# TD-01_Mk3.net
KiCad netlist of a schematic drawn in EasyEDA
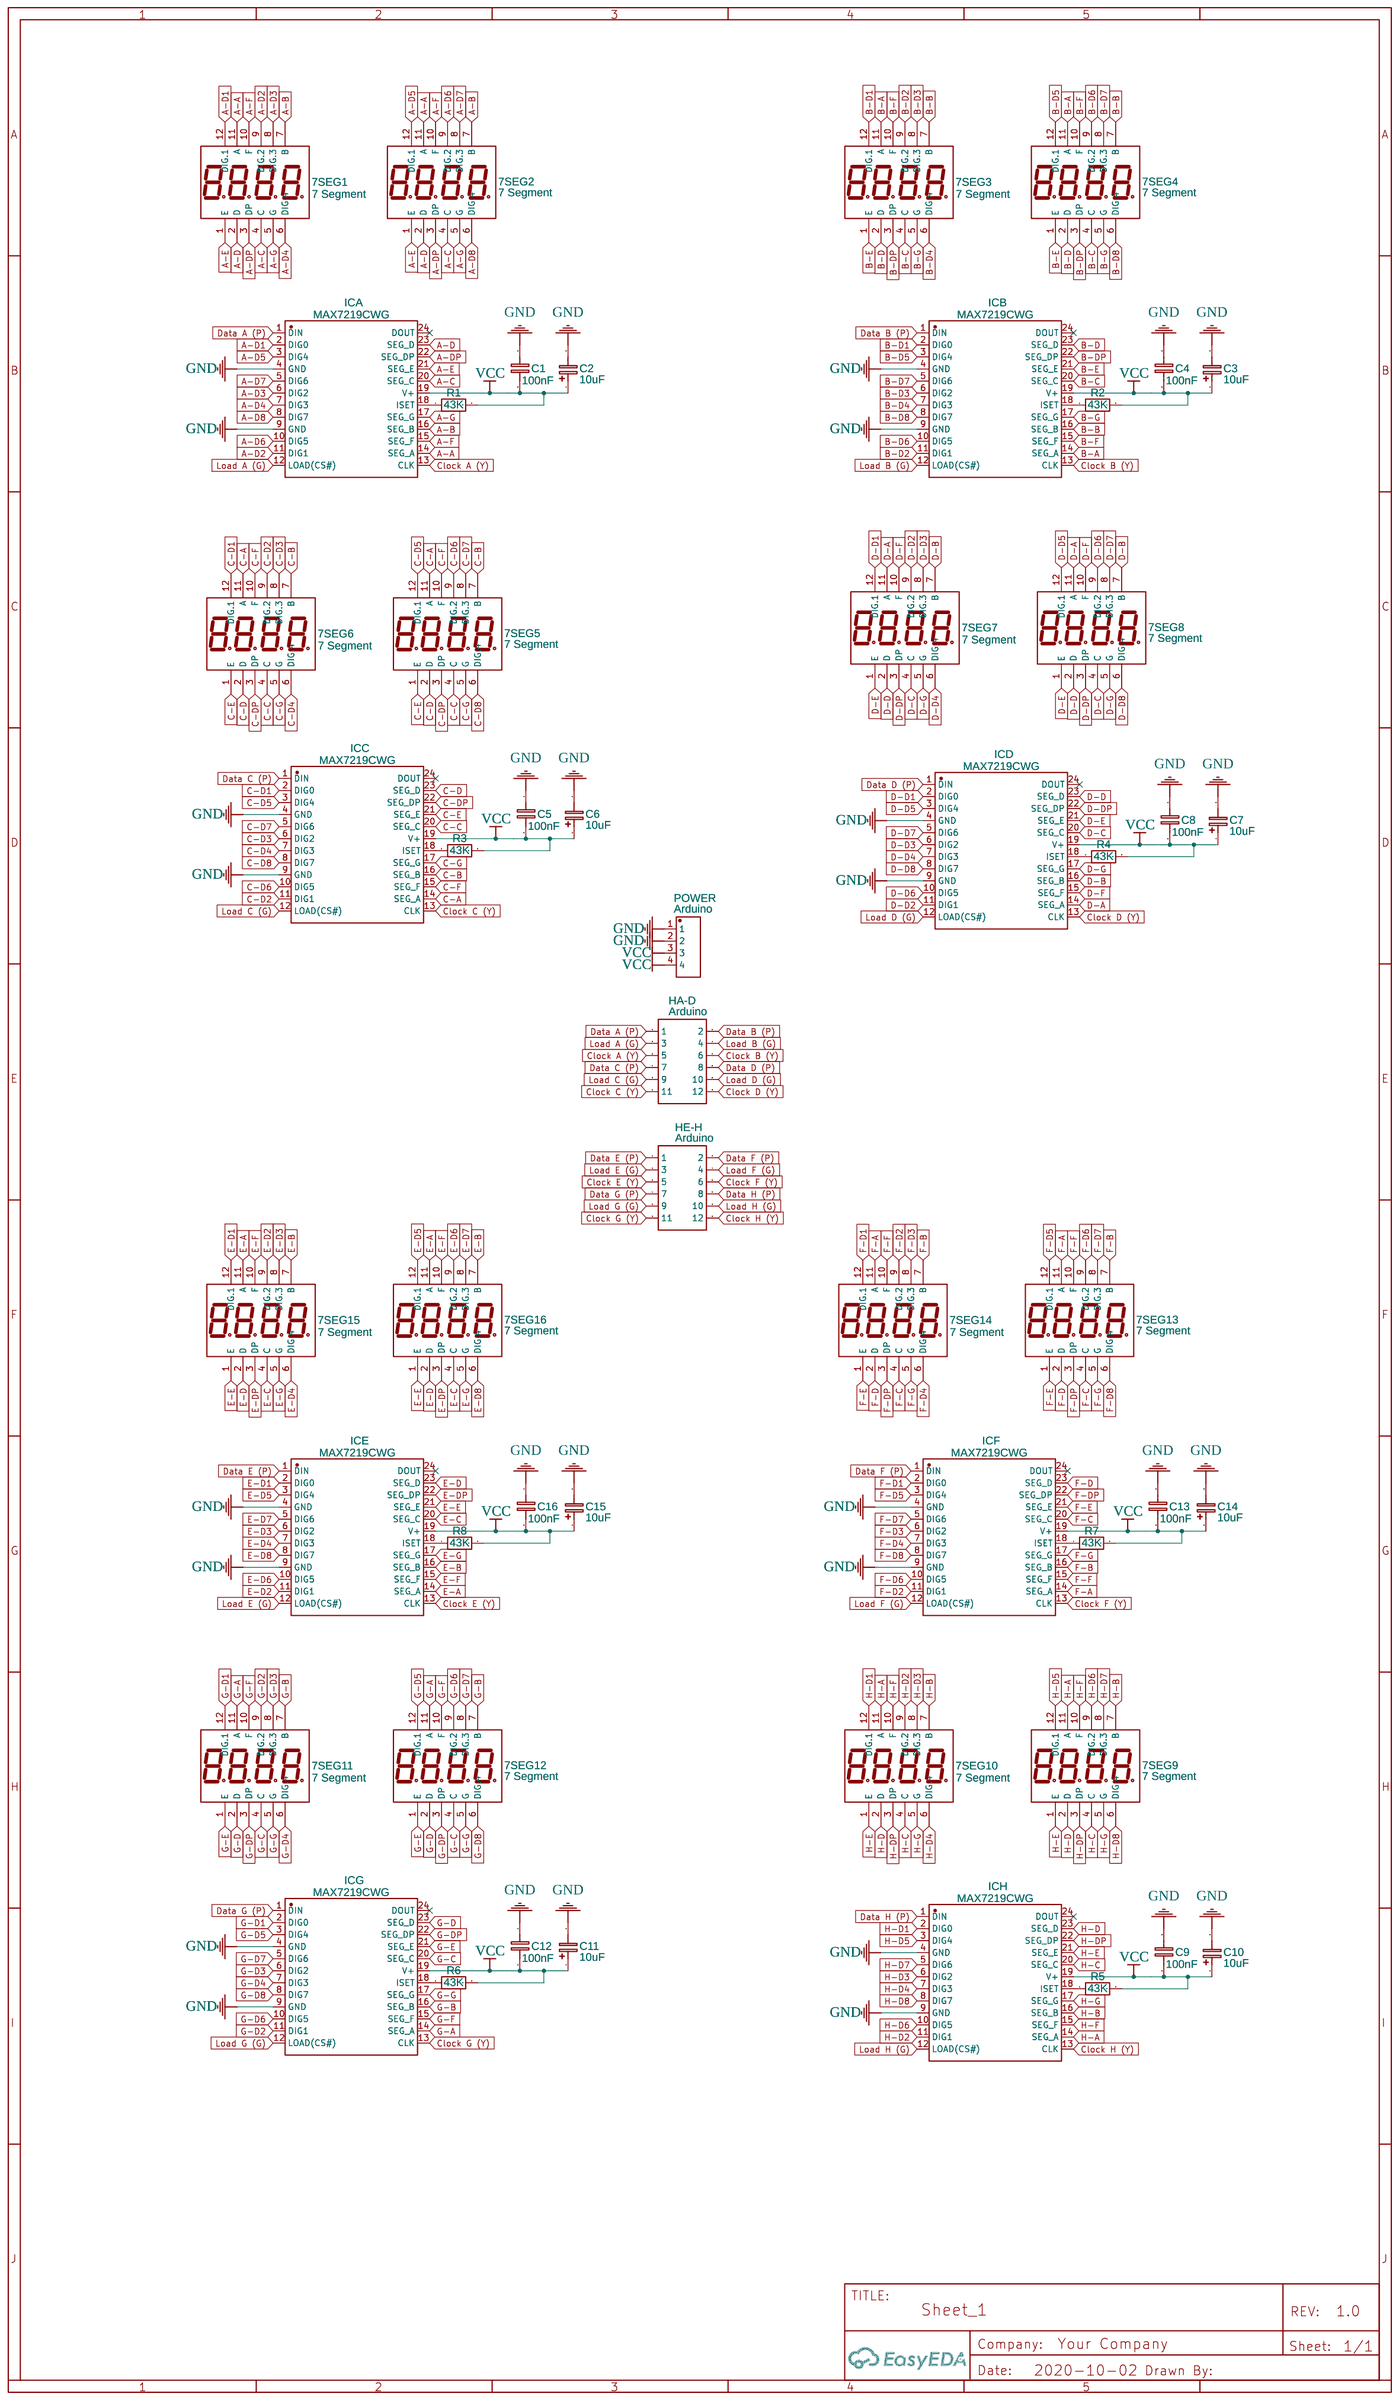
[diagram p0: schematic sheet]

(export (version "E")
  (design (tool "Eeschema 10.0.6"))
  (components
    (comp (ref "7SEG1")
      (value "7 Segment")
      (fields
        (field (name "BOM_Manufacturer Part") "TOF-5461AMR-B17.5")
        (field (name "BOM_Supplier Part") "C417345")
      )
      (libsource (lib "") (part "TOF-5461AMR-B17.5"))
    )
    (comp (ref "7SEG2")
      (value "7 Segment")
      (fields
        (field (name "BOM_Manufacturer Part") "TOF-5461AMR-B17.5")
        (field (name "BOM_Supplier Part") "C417345")
      )
      (libsource (lib "") (part "TOF-5461AMR-B17.5"))
    )
    (comp (ref "7SEG3")
      (value "7 Segment")
      (fields
        (field (name "BOM_Manufacturer Part") "TOF-5461AMR-B17.5")
        (field (name "BOM_Supplier Part") "C417345")
      )
      (libsource (lib "") (part "TOF-5461AMR-B17.5"))
    )
    (comp (ref "7SEG4")
      (value "7 Segment")
      (fields
        (field (name "BOM_Manufacturer Part") "TOF-5461AMR-B17.5")
        (field (name "BOM_Supplier Part") "C417345")
      )
      (libsource (lib "") (part "TOF-5461AMR-B17.5"))
    )
    (comp (ref "7SEG5")
      (value "7 Segment")
      (fields
        (field (name "BOM_Manufacturer Part") "TOF-5461AMR-B17.5")
        (field (name "BOM_Supplier Part") "C417345")
      )
      (libsource (lib "") (part "TOF-5461AMR-B17.5"))
    )
    (comp (ref "7SEG6")
      (value "7 Segment")
      (fields
        (field (name "BOM_Manufacturer Part") "TOF-5461AMR-B17.5")
        (field (name "BOM_Supplier Part") "C417345")
      )
      (libsource (lib "") (part "TOF-5461AMR-B17.5"))
    )
    (comp (ref "7SEG7")
      (value "7 Segment")
      (fields
        (field (name "BOM_Manufacturer Part") "TOF-5461AMR-B17.5")
        (field (name "BOM_Supplier Part") "C417345")
      )
      (libsource (lib "") (part "TOF-5461AMR-B17.5"))
    )
    (comp (ref "7SEG8")
      (value "7 Segment")
      (fields
        (field (name "BOM_Manufacturer Part") "TOF-5461AMR-B17.5")
        (field (name "BOM_Supplier Part") "C417345")
      )
      (libsource (lib "") (part "TOF-5461AMR-B17.5"))
    )
    (comp (ref "7SEG9")
      (value "7 Segment")
      (fields
        (field (name "BOM_Manufacturer Part") "TOF-5461AMR-B17.5")
        (field (name "BOM_Supplier Part") "C417345")
      )
      (libsource (lib "") (part "TOF-5461AMR-B17.5"))
    )
    (comp (ref "7SEG10")
      (value "7 Segment")
      (fields
        (field (name "BOM_Manufacturer Part") "TOF-5461AMR-B17.5")
        (field (name "BOM_Supplier Part") "C417345")
      )
      (libsource (lib "") (part "TOF-5461AMR-B17.5"))
    )
    (comp (ref "7SEG11")
      (value "7 Segment")
      (fields
        (field (name "BOM_Manufacturer Part") "TOF-5461AMR-B17.5")
        (field (name "BOM_Supplier Part") "C417345")
      )
      (libsource (lib "") (part "TOF-5461AMR-B17.5"))
    )
    (comp (ref "7SEG12")
      (value "7 Segment")
      (fields
        (field (name "BOM_Manufacturer Part") "TOF-5461AMR-B17.5")
        (field (name "BOM_Supplier Part") "C417345")
      )
      (libsource (lib "") (part "TOF-5461AMR-B17.5"))
    )
    (comp (ref "7SEG13")
      (value "7 Segment")
      (fields
        (field (name "BOM_Manufacturer Part") "TOF-5461AMR-B17.5")
        (field (name "BOM_Supplier Part") "C417345")
      )
      (libsource (lib "") (part "TOF-5461AMR-B17.5"))
    )
    (comp (ref "7SEG14")
      (value "7 Segment")
      (fields
        (field (name "BOM_Manufacturer Part") "TOF-5461AMR-B17.5")
        (field (name "BOM_Supplier Part") "C417345")
      )
      (libsource (lib "") (part "TOF-5461AMR-B17.5"))
    )
    (comp (ref "7SEG15")
      (value "7 Segment")
      (fields
        (field (name "BOM_Manufacturer Part") "TOF-5461AMR-B17.5")
        (field (name "BOM_Supplier Part") "C417345")
      )
      (libsource (lib "") (part "TOF-5461AMR-B17.5"))
    )
    (comp (ref "7SEG16")
      (value "7 Segment")
      (fields
        (field (name "BOM_Manufacturer Part") "TOF-5461AMR-B17.5")
        (field (name "BOM_Supplier Part") "C417345")
      )
      (libsource (lib "") (part "TOF-5461AMR-B17.5"))
    )
    (comp (ref "C1") (value "100nF") (libsource (lib "") (part "C_0603_EU_1")))
    (comp (ref "C2") (value "10uF") (libsource (lib "") (part "C_Tan_SMD_A_EU_5")))
    (comp (ref "C3") (value "10uF") (libsource (lib "") (part "C_Tan_SMD_A_EU_1")))
    (comp (ref "C4") (value "100nF") (libsource (lib "") (part "C_0603_EU_2")))
    (comp (ref "C5") (value "100nF") (libsource (lib "") (part "C_0603_EU_3")))
    (comp (ref "C6") (value "10uF") (libsource (lib "") (part "C_Tan_SMD_A_EU_4")))
    (comp (ref "C7") (value "10uF") (libsource (lib "") (part "C_Tan_SMD_A_EU_3")))
    (comp (ref "C8") (value "100nF") (libsource (lib "") (part "C_0603_EU")))
    (comp (ref "C9") (value "100nF") (libsource (lib "") (part "C_0603_EU")))
    (comp (ref "C10") (value "10uF") (libsource (lib "") (part "C_Tan_SMD_A_EU_2")))
    (comp (ref "C11") (value "10uF") (libsource (lib "") (part "C_Tan_SMD_A_EU")))
    (comp (ref "C12") (value "100nF") (libsource (lib "") (part "C_0603_EU_3")))
    (comp (ref "C13") (value "100nF") (libsource (lib "") (part "C_0603_EU")))
    (comp (ref "C14") (value "10uF") (libsource (lib "") (part "C_Tan_SMD_A_EU_2")))
    (comp (ref "C15") (value "10uF") (libsource (lib "") (part "C_Tan_SMD_A_EU")))
    (comp (ref "C16") (value "100nF") (libsource (lib "") (part "C_0603_EU_3")))
    (comp (ref "HA-D")
      (value "Arduino")
      (fields
        (field (name "BOM_Manufacturer Part") "Header-Female-2.54_2x6")
        (field (name "BOM_Supplier Part") "C36191")
      )
      (libsource (lib "") (part "Header-Female-2.54_2x6"))
    )
    (comp (ref "HE-H")
      (value "Arduino")
      (fields
        (field (name "BOM_Manufacturer Part") "Header-Female-2.54_2x6")
        (field (name "BOM_Supplier Part") "C36191")
      )
      (libsource (lib "") (part "Header-Female-2.54_2x6_1"))
    )
    (comp (ref "ICA")
      (value "MAX7219CWG")
      (fields (field (name "BOM_Supplier Part") "C9964"))
      (libsource (lib "") (part "MAX7219CWG_3"))
    )
    (comp (ref "ICB")
      (value "MAX7219CWG")
      (fields (field (name "BOM_Supplier Part") "C9964"))
      (libsource (lib "") (part "MAX7219CWG_7"))
    )
    (comp (ref "ICC")
      (value "MAX7219CWG")
      (fields (field (name "BOM_Supplier Part") "C9964"))
      (libsource (lib "") (part "MAX7219CWG_6"))
    )
    (comp (ref "ICD")
      (value "MAX7219CWG")
      (fields (field (name "BOM_Supplier Part") "C9964"))
      (libsource (lib "") (part "MAX7219CWG_5"))
    )
    (comp (ref "ICE")
      (value "MAX7219CWG")
      (fields (field (name "BOM_Supplier Part") "C9964"))
      (libsource (lib "") (part "MAX7219CWG_4"))
    )
    (comp (ref "ICF")
      (value "MAX7219CWG")
      (fields (field (name "BOM_Supplier Part") "C9964"))
      (libsource (lib "") (part "MAX7219CWG_1"))
    )
    (comp (ref "ICG")
      (value "MAX7219CWG")
      (fields (field (name "BOM_Supplier Part") "C9964"))
      (libsource (lib "") (part "MAX7219CWG"))
    )
    (comp (ref "ICH")
      (value "MAX7219CWG")
      (fields (field (name "BOM_Supplier Part") "C9964"))
      (libsource (lib "") (part "MAX7219CWG_2"))
    )
    (comp (ref "POWER")
      (value "Arduino")
      (fields
        (field (name "BOM_Manufacturer Part") "Headers  Pins 1*4P")
        (field (name "BOM_Supplier Part") "C59481")
      )
      (libsource (lib "") (part "Header-Male-2.54_1x4_C59481"))
    )
    (comp (ref "R1") (value "43K") (libsource (lib "") (part "R_0603_EU")))
    (comp (ref "R2") (value "43K") (libsource (lib "") (part "R_0603_EU")))
    (comp (ref "R3") (value "43K") (libsource (lib "") (part "R_0603_EU")))
    (comp (ref "R4") (value "43K") (libsource (lib "") (part "R_0603_EU")))
    (comp (ref "R5") (value "43K") (libsource (lib "") (part "R_0603_EU")))
    (comp (ref "R6") (value "43K") (libsource (lib "") (part "R_0603_EU")))
    (comp (ref "R7") (value "43K") (libsource (lib "") (part "R_0603_EU")))
    (comp (ref "R8") (value "43K") (libsource (lib "") (part "R_0603_EU")))
  )
  (nets
    (net (code "1") (name "A-A") (class "Default")
      (node (ref "7SEG1") (pin "11") (pinfunction "A_11") (pintype "unspecified"))
      (node (ref "7SEG2") (pin "11") (pinfunction "A_11") (pintype "unspecified"))
      (node (ref "ICA") (pin "14") (pinfunction "SEG_A_14") (pintype "unspecified"))
    )
    (net (code "2") (name "A-B") (class "Default")
      (node (ref "7SEG1") (pin "7") (pinfunction "B_7") (pintype "unspecified"))
      (node (ref "7SEG2") (pin "7") (pinfunction "B_7") (pintype "unspecified"))
      (node (ref "ICA") (pin "16") (pinfunction "SEG_B_16") (pintype "unspecified"))
    )
    (net (code "3") (name "A-C") (class "Default")
      (node (ref "7SEG1") (pin "4") (pinfunction "C_4") (pintype "unspecified"))
      (node (ref "7SEG2") (pin "4") (pinfunction "C_4") (pintype "unspecified"))
      (node (ref "ICA") (pin "20") (pinfunction "SEG_C_20") (pintype "unspecified"))
    )
    (net (code "4") (name "A-D") (class "Default")
      (node (ref "7SEG1") (pin "2") (pinfunction "D_2") (pintype "unspecified"))
      (node (ref "7SEG2") (pin "2") (pinfunction "D_2") (pintype "unspecified"))
      (node (ref "ICA") (pin "23") (pinfunction "SEG_D_23") (pintype "unspecified"))
    )
    (net (code "5") (name "A-D1") (class "Default")
      (node (ref "7SEG1") (pin "12") (pinfunction "DIG.1_12") (pintype "unspecified"))
      (node (ref "ICA") (pin "2") (pinfunction "DIG0_2") (pintype "unspecified"))
    )
    (net (code "6") (name "A-D2") (class "Default")
      (node (ref "7SEG1") (pin "9") (pinfunction "DIG.2_9") (pintype "unspecified"))
      (node (ref "ICA") (pin "11") (pinfunction "DIG1_11") (pintype "unspecified"))
    )
    (net (code "7") (name "A-D3") (class "Default")
      (node (ref "7SEG1") (pin "8") (pinfunction "DIG.3_8") (pintype "unspecified"))
      (node (ref "ICA") (pin "6") (pinfunction "DIG2_6") (pintype "unspecified"))
    )
    (net (code "8") (name "A-D4") (class "Default")
      (node (ref "7SEG1") (pin "6") (pinfunction "DIG.4_6") (pintype "unspecified"))
      (node (ref "ICA") (pin "7") (pinfunction "DIG3_7") (pintype "unspecified"))
    )
    (net (code "9") (name "A-D5") (class "Default")
      (node (ref "7SEG2") (pin "12") (pinfunction "DIG.1_12") (pintype "unspecified"))
      (node (ref "ICA") (pin "3") (pinfunction "DIG4_3") (pintype "unspecified"))
    )
    (net (code "10") (name "A-D6") (class "Default")
      (node (ref "7SEG2") (pin "9") (pinfunction "DIG.2_9") (pintype "unspecified"))
      (node (ref "ICA") (pin "10") (pinfunction "DIG5_10") (pintype "unspecified"))
    )
    (net (code "11") (name "A-D7") (class "Default")
      (node (ref "7SEG2") (pin "8") (pinfunction "DIG.3_8") (pintype "unspecified"))
      (node (ref "ICA") (pin "5") (pinfunction "DIG6_5") (pintype "unspecified"))
    )
    (net (code "12") (name "A-D8") (class "Default")
      (node (ref "7SEG2") (pin "6") (pinfunction "DIG.4_6") (pintype "unspecified"))
      (node (ref "ICA") (pin "8") (pinfunction "DIG7_8") (pintype "unspecified"))
    )
    (net (code "13") (name "A-DP") (class "Default")
      (node (ref "7SEG1") (pin "3") (pinfunction "DP_3") (pintype "unspecified"))
      (node (ref "7SEG2") (pin "3") (pinfunction "DP_3") (pintype "unspecified"))
      (node (ref "ICA") (pin "22") (pinfunction "SEG_DP_22") (pintype "unspecified"))
    )
    (net (code "14") (name "A-E") (class "Default")
      (node (ref "7SEG1") (pin "1") (pinfunction "E_1") (pintype "unspecified"))
      (node (ref "7SEG2") (pin "1") (pinfunction "E_1") (pintype "unspecified"))
      (node (ref "ICA") (pin "21") (pinfunction "SEG_E_21") (pintype "unspecified"))
    )
    (net (code "15") (name "A-F") (class "Default")
      (node (ref "7SEG1") (pin "10") (pinfunction "F_10") (pintype "unspecified"))
      (node (ref "7SEG2") (pin "10") (pinfunction "F_10") (pintype "unspecified"))
      (node (ref "ICA") (pin "15") (pinfunction "SEG_F_15") (pintype "unspecified"))
    )
    (net (code "16") (name "A-G") (class "Default")
      (node (ref "7SEG1") (pin "5") (pinfunction "G_5") (pintype "unspecified"))
      (node (ref "7SEG2") (pin "5") (pinfunction "G_5") (pintype "unspecified"))
      (node (ref "ICA") (pin "17") (pinfunction "SEG_G_17") (pintype "unspecified"))
    )
    (net (code "17") (name "B-A") (class "Default")
      (node (ref "7SEG3") (pin "11") (pinfunction "A_11") (pintype "unspecified"))
      (node (ref "7SEG4") (pin "11") (pinfunction "A_11") (pintype "unspecified"))
      (node (ref "ICB") (pin "14") (pinfunction "SEG_A_14") (pintype "unspecified"))
    )
    (net (code "18") (name "B-B") (class "Default")
      (node (ref "7SEG3") (pin "7") (pinfunction "B_7") (pintype "unspecified"))
      (node (ref "7SEG4") (pin "7") (pinfunction "B_7") (pintype "unspecified"))
      (node (ref "ICB") (pin "16") (pinfunction "SEG_B_16") (pintype "unspecified"))
    )
    (net (code "19") (name "B-C") (class "Default")
      (node (ref "7SEG3") (pin "4") (pinfunction "C_4") (pintype "unspecified"))
      (node (ref "7SEG4") (pin "4") (pinfunction "C_4") (pintype "unspecified"))
      (node (ref "ICB") (pin "20") (pinfunction "SEG_C_20") (pintype "unspecified"))
    )
    (net (code "20") (name "B-D") (class "Default")
      (node (ref "7SEG3") (pin "2") (pinfunction "D_2") (pintype "unspecified"))
      (node (ref "7SEG4") (pin "2") (pinfunction "D_2") (pintype "unspecified"))
      (node (ref "ICB") (pin "23") (pinfunction "SEG_D_23") (pintype "unspecified"))
    )
    (net (code "21") (name "B-D1") (class "Default")
      (node (ref "7SEG3") (pin "12") (pinfunction "DIG.1_12") (pintype "unspecified"))
      (node (ref "ICB") (pin "2") (pinfunction "DIG0_2") (pintype "unspecified"))
    )
    (net (code "22") (name "B-D2") (class "Default")
      (node (ref "7SEG3") (pin "9") (pinfunction "DIG.2_9") (pintype "unspecified"))
      (node (ref "ICB") (pin "11") (pinfunction "DIG1_11") (pintype "unspecified"))
    )
    (net (code "23") (name "B-D3") (class "Default")
      (node (ref "7SEG3") (pin "8") (pinfunction "DIG.3_8") (pintype "unspecified"))
      (node (ref "ICB") (pin "6") (pinfunction "DIG2_6") (pintype "unspecified"))
    )
    (net (code "24") (name "B-D4") (class "Default")
      (node (ref "7SEG3") (pin "6") (pinfunction "DIG.4_6") (pintype "unspecified"))
      (node (ref "ICB") (pin "7") (pinfunction "DIG3_7") (pintype "unspecified"))
    )
    (net (code "25") (name "B-D5") (class "Default")
      (node (ref "7SEG4") (pin "12") (pinfunction "DIG.1_12") (pintype "unspecified"))
      (node (ref "ICB") (pin "3") (pinfunction "DIG4_3") (pintype "unspecified"))
    )
    (net (code "26") (name "B-D6") (class "Default")
      (node (ref "7SEG4") (pin "9") (pinfunction "DIG.2_9") (pintype "unspecified"))
      (node (ref "ICB") (pin "10") (pinfunction "DIG5_10") (pintype "unspecified"))
    )
    (net (code "27") (name "B-D7") (class "Default")
      (node (ref "7SEG4") (pin "8") (pinfunction "DIG.3_8") (pintype "unspecified"))
      (node (ref "ICB") (pin "5") (pinfunction "DIG6_5") (pintype "unspecified"))
    )
    (net (code "28") (name "B-D8") (class "Default")
      (node (ref "7SEG4") (pin "6") (pinfunction "DIG.4_6") (pintype "unspecified"))
      (node (ref "ICB") (pin "8") (pinfunction "DIG7_8") (pintype "unspecified"))
    )
    (net (code "29") (name "B-DP") (class "Default")
      (node (ref "7SEG3") (pin "3") (pinfunction "DP_3") (pintype "unspecified"))
      (node (ref "7SEG4") (pin "3") (pinfunction "DP_3") (pintype "unspecified"))
      (node (ref "ICB") (pin "22") (pinfunction "SEG_DP_22") (pintype "unspecified"))
    )
    (net (code "30") (name "B-E") (class "Default")
      (node (ref "7SEG3") (pin "1") (pinfunction "E_1") (pintype "unspecified"))
      (node (ref "7SEG4") (pin "1") (pinfunction "E_1") (pintype "unspecified"))
      (node (ref "ICB") (pin "21") (pinfunction "SEG_E_21") (pintype "unspecified"))
    )
    (net (code "31") (name "B-F") (class "Default")
      (node (ref "7SEG3") (pin "10") (pinfunction "F_10") (pintype "unspecified"))
      (node (ref "7SEG4") (pin "10") (pinfunction "F_10") (pintype "unspecified"))
      (node (ref "ICB") (pin "15") (pinfunction "SEG_F_15") (pintype "unspecified"))
    )
    (net (code "32") (name "B-G") (class "Default")
      (node (ref "7SEG3") (pin "5") (pinfunction "G_5") (pintype "unspecified"))
      (node (ref "7SEG4") (pin "5") (pinfunction "G_5") (pintype "unspecified"))
      (node (ref "ICB") (pin "17") (pinfunction "SEG_G_17") (pintype "unspecified"))
    )
    (net (code "33") (name "C-A") (class "Default")
      (node (ref "7SEG5") (pin "11") (pinfunction "A_11") (pintype "unspecified"))
      (node (ref "7SEG6") (pin "11") (pinfunction "A_11") (pintype "unspecified"))
      (node (ref "ICC") (pin "14") (pinfunction "SEG_A_14") (pintype "unspecified"))
    )
    (net (code "34") (name "C-B") (class "Default")
      (node (ref "7SEG5") (pin "7") (pinfunction "B_7") (pintype "unspecified"))
      (node (ref "7SEG6") (pin "7") (pinfunction "B_7") (pintype "unspecified"))
      (node (ref "ICC") (pin "16") (pinfunction "SEG_B_16") (pintype "unspecified"))
    )
    (net (code "35") (name "C-C") (class "Default")
      (node (ref "7SEG5") (pin "4") (pinfunction "C_4") (pintype "unspecified"))
      (node (ref "7SEG6") (pin "4") (pinfunction "C_4") (pintype "unspecified"))
      (node (ref "ICC") (pin "20") (pinfunction "SEG_C_20") (pintype "unspecified"))
    )
    (net (code "36") (name "C-D") (class "Default")
      (node (ref "7SEG5") (pin "2") (pinfunction "D_2") (pintype "unspecified"))
      (node (ref "7SEG6") (pin "2") (pinfunction "D_2") (pintype "unspecified"))
      (node (ref "ICC") (pin "23") (pinfunction "SEG_D_23") (pintype "unspecified"))
    )
    (net (code "37") (name "C-D1") (class "Default")
      (node (ref "7SEG6") (pin "12") (pinfunction "DIG.1_12") (pintype "unspecified"))
      (node (ref "ICC") (pin "2") (pinfunction "DIG0_2") (pintype "unspecified"))
    )
    (net (code "38") (name "C-D2") (class "Default")
      (node (ref "7SEG6") (pin "9") (pinfunction "DIG.2_9") (pintype "unspecified"))
      (node (ref "ICC") (pin "11") (pinfunction "DIG1_11") (pintype "unspecified"))
    )
    (net (code "39") (name "C-D3") (class "Default")
      (node (ref "7SEG6") (pin "8") (pinfunction "DIG.3_8") (pintype "unspecified"))
      (node (ref "ICC") (pin "6") (pinfunction "DIG2_6") (pintype "unspecified"))
    )
    (net (code "40") (name "C-D4") (class "Default")
      (node (ref "7SEG6") (pin "6") (pinfunction "DIG.4_6") (pintype "unspecified"))
      (node (ref "ICC") (pin "7") (pinfunction "DIG3_7") (pintype "unspecified"))
    )
    (net (code "41") (name "C-D5") (class "Default")
      (node (ref "7SEG5") (pin "12") (pinfunction "DIG.1_12") (pintype "unspecified"))
      (node (ref "ICC") (pin "3") (pinfunction "DIG4_3") (pintype "unspecified"))
    )
    (net (code "42") (name "C-D6") (class "Default")
      (node (ref "7SEG5") (pin "9") (pinfunction "DIG.2_9") (pintype "unspecified"))
      (node (ref "ICC") (pin "10") (pinfunction "DIG5_10") (pintype "unspecified"))
    )
    (net (code "43") (name "C-D7") (class "Default")
      (node (ref "7SEG5") (pin "8") (pinfunction "DIG.3_8") (pintype "unspecified"))
      (node (ref "ICC") (pin "5") (pinfunction "DIG6_5") (pintype "unspecified"))
    )
    (net (code "44") (name "C-D8") (class "Default")
      (node (ref "7SEG5") (pin "6") (pinfunction "DIG.4_6") (pintype "unspecified"))
      (node (ref "ICC") (pin "8") (pinfunction "DIG7_8") (pintype "unspecified"))
    )
    (net (code "45") (name "C-DP") (class "Default")
      (node (ref "7SEG5") (pin "3") (pinfunction "DP_3") (pintype "unspecified"))
      (node (ref "7SEG6") (pin "3") (pinfunction "DP_3") (pintype "unspecified"))
      (node (ref "ICC") (pin "22") (pinfunction "SEG_DP_22") (pintype "unspecified"))
    )
    (net (code "46") (name "C-E") (class "Default")
      (node (ref "7SEG5") (pin "1") (pinfunction "E_1") (pintype "unspecified"))
      (node (ref "7SEG6") (pin "1") (pinfunction "E_1") (pintype "unspecified"))
      (node (ref "ICC") (pin "21") (pinfunction "SEG_E_21") (pintype "unspecified"))
    )
    (net (code "47") (name "C-F") (class "Default")
      (node (ref "7SEG5") (pin "10") (pinfunction "F_10") (pintype "unspecified"))
      (node (ref "7SEG6") (pin "10") (pinfunction "F_10") (pintype "unspecified"))
      (node (ref "ICC") (pin "15") (pinfunction "SEG_F_15") (pintype "unspecified"))
    )
    (net (code "48") (name "C-G") (class "Default")
      (node (ref "7SEG5") (pin "5") (pinfunction "G_5") (pintype "unspecified"))
      (node (ref "7SEG6") (pin "5") (pinfunction "G_5") (pintype "unspecified"))
      (node (ref "ICC") (pin "17") (pinfunction "SEG_G_17") (pintype "unspecified"))
    )
    (net (code "49") (name "Clock A (Y)") (class "Default")
      (node (ref "HA-D") (pin "5") (pinfunction "5_5") (pintype "input"))
      (node (ref "ICA") (pin "13") (pinfunction "CLK_13") (pintype "unspecified"))
    )
    (net (code "50") (name "Clock B (Y)") (class "Default")
      (node (ref "HA-D") (pin "6") (pinfunction "6_6") (pintype "input"))
      (node (ref "ICB") (pin "13") (pinfunction "CLK_13") (pintype "unspecified"))
    )
    (net (code "51") (name "Clock C (Y)") (class "Default")
      (node (ref "HA-D") (pin "11") (pinfunction "11_11") (pintype "input"))
      (node (ref "ICC") (pin "13") (pinfunction "CLK_13") (pintype "unspecified"))
    )
    (net (code "52") (name "Clock D (Y)") (class "Default")
      (node (ref "HA-D") (pin "12") (pinfunction "12_12") (pintype "input"))
      (node (ref "ICD") (pin "13") (pinfunction "CLK_13") (pintype "unspecified"))
    )
    (net (code "53") (name "Clock E (Y)") (class "Default")
      (node (ref "HE-H") (pin "5") (pinfunction "5_5") (pintype "input"))
      (node (ref "ICE") (pin "13") (pinfunction "CLK_13") (pintype "unspecified"))
    )
    (net (code "54") (name "Clock F (Y)") (class "Default")
      (node (ref "HE-H") (pin "6") (pinfunction "6_6") (pintype "input"))
      (node (ref "ICF") (pin "13") (pinfunction "CLK_13") (pintype "unspecified"))
    )
    (net (code "55") (name "Clock G (Y)") (class "Default")
      (node (ref "HE-H") (pin "11") (pinfunction "11_11") (pintype "input"))
      (node (ref "ICG") (pin "13") (pinfunction "CLK_13") (pintype "unspecified"))
    )
    (net (code "56") (name "Clock H (Y)") (class "Default")
      (node (ref "HE-H") (pin "12") (pinfunction "12_12") (pintype "input"))
      (node (ref "ICH") (pin "13") (pinfunction "CLK_13") (pintype "unspecified"))
    )
    (net (code "57") (name "D-A") (class "Default")
      (node (ref "7SEG7") (pin "11") (pinfunction "A_11") (pintype "unspecified"))
      (node (ref "7SEG8") (pin "11") (pinfunction "A_11") (pintype "unspecified"))
      (node (ref "ICD") (pin "14") (pinfunction "SEG_A_14") (pintype "unspecified"))
    )
    (net (code "58") (name "D-B") (class "Default")
      (node (ref "7SEG7") (pin "7") (pinfunction "B_7") (pintype "unspecified"))
      (node (ref "7SEG8") (pin "7") (pinfunction "B_7") (pintype "unspecified"))
      (node (ref "ICD") (pin "16") (pinfunction "SEG_B_16") (pintype "unspecified"))
    )
    (net (code "59") (name "D-C") (class "Default")
      (node (ref "7SEG7") (pin "4") (pinfunction "C_4") (pintype "unspecified"))
      (node (ref "7SEG8") (pin "4") (pinfunction "C_4") (pintype "unspecified"))
      (node (ref "ICD") (pin "20") (pinfunction "SEG_C_20") (pintype "unspecified"))
    )
    (net (code "60") (name "D-D") (class "Default")
      (node (ref "7SEG7") (pin "2") (pinfunction "D_2") (pintype "unspecified"))
      (node (ref "7SEG8") (pin "2") (pinfunction "D_2") (pintype "unspecified"))
      (node (ref "ICD") (pin "23") (pinfunction "SEG_D_23") (pintype "unspecified"))
    )
    (net (code "61") (name "D-D1") (class "Default")
      (node (ref "7SEG7") (pin "12") (pinfunction "DIG.1_12") (pintype "unspecified"))
      (node (ref "ICD") (pin "2") (pinfunction "DIG0_2") (pintype "unspecified"))
    )
    (net (code "62") (name "D-D2") (class "Default")
      (node (ref "7SEG7") (pin "9") (pinfunction "DIG.2_9") (pintype "unspecified"))
      (node (ref "ICD") (pin "11") (pinfunction "DIG1_11") (pintype "unspecified"))
    )
    (net (code "63") (name "D-D3") (class "Default")
      (node (ref "7SEG7") (pin "8") (pinfunction "DIG.3_8") (pintype "unspecified"))
      (node (ref "ICD") (pin "6") (pinfunction "DIG2_6") (pintype "unspecified"))
    )
    (net (code "64") (name "D-D4") (class "Default")
      (node (ref "7SEG7") (pin "6") (pinfunction "DIG.4_6") (pintype "unspecified"))
      (node (ref "ICD") (pin "7") (pinfunction "DIG3_7") (pintype "unspecified"))
    )
    (net (code "65") (name "D-D5") (class "Default")
      (node (ref "7SEG8") (pin "12") (pinfunction "DIG.1_12") (pintype "unspecified"))
      (node (ref "ICD") (pin "3") (pinfunction "DIG4_3") (pintype "unspecified"))
    )
    (net (code "66") (name "D-D6") (class "Default")
      (node (ref "7SEG8") (pin "9") (pinfunction "DIG.2_9") (pintype "unspecified"))
      (node (ref "ICD") (pin "10") (pinfunction "DIG5_10") (pintype "unspecified"))
    )
    (net (code "67") (name "D-D7") (class "Default")
      (node (ref "7SEG8") (pin "8") (pinfunction "DIG.3_8") (pintype "unspecified"))
      (node (ref "ICD") (pin "5") (pinfunction "DIG6_5") (pintype "unspecified"))
    )
    (net (code "68") (name "D-D8") (class "Default")
      (node (ref "7SEG8") (pin "6") (pinfunction "DIG.4_6") (pintype "unspecified"))
      (node (ref "ICD") (pin "8") (pinfunction "DIG7_8") (pintype "unspecified"))
    )
    (net (code "69") (name "D-DP") (class "Default")
      (node (ref "7SEG7") (pin "3") (pinfunction "DP_3") (pintype "unspecified"))
      (node (ref "7SEG8") (pin "3") (pinfunction "DP_3") (pintype "unspecified"))
      (node (ref "ICD") (pin "22") (pinfunction "SEG_DP_22") (pintype "unspecified"))
    )
    (net (code "70") (name "D-E") (class "Default")
      (node (ref "7SEG7") (pin "1") (pinfunction "E_1") (pintype "unspecified"))
      (node (ref "7SEG8") (pin "1") (pinfunction "E_1") (pintype "unspecified"))
      (node (ref "ICD") (pin "21") (pinfunction "SEG_E_21") (pintype "unspecified"))
    )
    (net (code "71") (name "D-F") (class "Default")
      (node (ref "7SEG7") (pin "10") (pinfunction "F_10") (pintype "unspecified"))
      (node (ref "7SEG8") (pin "10") (pinfunction "F_10") (pintype "unspecified"))
      (node (ref "ICD") (pin "15") (pinfunction "SEG_F_15") (pintype "unspecified"))
    )
    (net (code "72") (name "D-G") (class "Default")
      (node (ref "7SEG7") (pin "5") (pinfunction "G_5") (pintype "unspecified"))
      (node (ref "7SEG8") (pin "5") (pinfunction "G_5") (pintype "unspecified"))
      (node (ref "ICD") (pin "17") (pinfunction "SEG_G_17") (pintype "unspecified"))
    )
    (net (code "73") (name "Data A (P)") (class "Default")
      (node (ref "HA-D") (pin "1") (pinfunction "1_1") (pintype "input"))
      (node (ref "ICA") (pin "1") (pinfunction "DIN_1") (pintype "unspecified"))
    )
    (net (code "74") (name "Data B (P)") (class "Default")
      (node (ref "HA-D") (pin "2") (pinfunction "2_2") (pintype "input"))
      (node (ref "ICB") (pin "1") (pinfunction "DIN_1") (pintype "unspecified"))
    )
    (net (code "75") (name "Data C (P)") (class "Default")
      (node (ref "HA-D") (pin "7") (pinfunction "7_7") (pintype "input"))
      (node (ref "ICC") (pin "1") (pinfunction "DIN_1") (pintype "unspecified"))
    )
    (net (code "76") (name "Data D (P)") (class "Default")
      (node (ref "HA-D") (pin "8") (pinfunction "8_8") (pintype "input"))
      (node (ref "ICD") (pin "1") (pinfunction "DIN_1") (pintype "unspecified"))
    )
    (net (code "77") (name "Data E (P)") (class "Default")
      (node (ref "HE-H") (pin "1") (pinfunction "1_1") (pintype "input"))
      (node (ref "ICE") (pin "1") (pinfunction "DIN_1") (pintype "unspecified"))
    )
    (net (code "78") (name "Data F (P)") (class "Default")
      (node (ref "HE-H") (pin "2") (pinfunction "2_2") (pintype "input"))
      (node (ref "ICF") (pin "1") (pinfunction "DIN_1") (pintype "unspecified"))
    )
    (net (code "79") (name "Data G (P)") (class "Default")
      (node (ref "HE-H") (pin "7") (pinfunction "7_7") (pintype "input"))
      (node (ref "ICG") (pin "1") (pinfunction "DIN_1") (pintype "unspecified"))
    )
    (net (code "80") (name "Data H (P)") (class "Default")
      (node (ref "HE-H") (pin "8") (pinfunction "8_8") (pintype "input"))
      (node (ref "ICH") (pin "1") (pinfunction "DIN_1") (pintype "unspecified"))
    )
    (net (code "81") (name "E-A") (class "Default")
      (node (ref "7SEG15") (pin "11") (pinfunction "A_11") (pintype "unspecified"))
      (node (ref "7SEG16") (pin "11") (pinfunction "A_11") (pintype "unspecified"))
      (node (ref "ICE") (pin "14") (pinfunction "SEG_A_14") (pintype "unspecified"))
    )
    (net (code "82") (name "E-B") (class "Default")
      (node (ref "7SEG15") (pin "7") (pinfunction "B_7") (pintype "unspecified"))
      (node (ref "7SEG16") (pin "7") (pinfunction "B_7") (pintype "unspecified"))
      (node (ref "ICE") (pin "16") (pinfunction "SEG_B_16") (pintype "unspecified"))
    )
    (net (code "83") (name "E-C") (class "Default")
      (node (ref "7SEG15") (pin "4") (pinfunction "C_4") (pintype "unspecified"))
      (node (ref "7SEG16") (pin "4") (pinfunction "C_4") (pintype "unspecified"))
      (node (ref "ICE") (pin "20") (pinfunction "SEG_C_20") (pintype "unspecified"))
    )
    (net (code "84") (name "E-D") (class "Default")
      (node (ref "7SEG15") (pin "2") (pinfunction "D_2") (pintype "unspecified"))
      (node (ref "7SEG16") (pin "2") (pinfunction "D_2") (pintype "unspecified"))
      (node (ref "ICE") (pin "23") (pinfunction "SEG_D_23") (pintype "unspecified"))
    )
    (net (code "85") (name "E-D1") (class "Default")
      (node (ref "7SEG15") (pin "12") (pinfunction "DIG.1_12") (pintype "unspecified"))
      (node (ref "ICE") (pin "2") (pinfunction "DIG0_2") (pintype "unspecified"))
    )
    (net (code "86") (name "E-D2") (class "Default")
      (node (ref "7SEG15") (pin "9") (pinfunction "DIG.2_9") (pintype "unspecified"))
      (node (ref "ICE") (pin "11") (pinfunction "DIG1_11") (pintype "unspecified"))
    )
    (net (code "87") (name "E-D3") (class "Default")
      (node (ref "7SEG15") (pin "8") (pinfunction "DIG.3_8") (pintype "unspecified"))
      (node (ref "ICE") (pin "6") (pinfunction "DIG2_6") (pintype "unspecified"))
    )
    (net (code "88") (name "E-D4") (class "Default")
      (node (ref "7SEG15") (pin "6") (pinfunction "DIG.4_6") (pintype "unspecified"))
      (node (ref "ICE") (pin "7") (pinfunction "DIG3_7") (pintype "unspecified"))
    )
    (net (code "89") (name "E-D5") (class "Default")
      (node (ref "7SEG16") (pin "12") (pinfunction "DIG.1_12") (pintype "unspecified"))
      (node (ref "ICE") (pin "3") (pinfunction "DIG4_3") (pintype "unspecified"))
    )
    (net (code "90") (name "E-D6") (class "Default")
      (node (ref "7SEG16") (pin "9") (pinfunction "DIG.2_9") (pintype "unspecified"))
      (node (ref "ICE") (pin "10") (pinfunction "DIG5_10") (pintype "unspecified"))
    )
    (net (code "91") (name "E-D7") (class "Default")
      (node (ref "7SEG16") (pin "8") (pinfunction "DIG.3_8") (pintype "unspecified"))
      (node (ref "ICE") (pin "5") (pinfunction "DIG6_5") (pintype "unspecified"))
    )
    (net (code "92") (name "E-D8") (class "Default")
      (node (ref "7SEG16") (pin "6") (pinfunction "DIG.4_6") (pintype "unspecified"))
      (node (ref "ICE") (pin "8") (pinfunction "DIG7_8") (pintype "unspecified"))
    )
    (net (code "93") (name "E-DP") (class "Default")
      (node (ref "7SEG15") (pin "3") (pinfunction "DP_3") (pintype "unspecified"))
      (node (ref "7SEG16") (pin "3") (pinfunction "DP_3") (pintype "unspecified"))
      (node (ref "ICE") (pin "22") (pinfunction "SEG_DP_22") (pintype "unspecified"))
    )
    (net (code "94") (name "E-E") (class "Default")
      (node (ref "7SEG15") (pin "1") (pinfunction "E_1") (pintype "unspecified"))
      (node (ref "7SEG16") (pin "1") (pinfunction "E_1") (pintype "unspecified"))
      (node (ref "ICE") (pin "21") (pinfunction "SEG_E_21") (pintype "unspecified"))
    )
    (net (code "95") (name "E-F") (class "Default")
      (node (ref "7SEG15") (pin "10") (pinfunction "F_10") (pintype "unspecified"))
      (node (ref "7SEG16") (pin "10") (pinfunction "F_10") (pintype "unspecified"))
      (node (ref "ICE") (pin "15") (pinfunction "SEG_F_15") (pintype "unspecified"))
    )
    (net (code "96") (name "E-G") (class "Default")
      (node (ref "7SEG15") (pin "5") (pinfunction "G_5") (pintype "unspecified"))
      (node (ref "7SEG16") (pin "5") (pinfunction "G_5") (pintype "unspecified"))
      (node (ref "ICE") (pin "17") (pinfunction "SEG_G_17") (pintype "unspecified"))
    )
    (net (code "97") (name "F-A") (class "Default")
      (node (ref "7SEG13") (pin "11") (pinfunction "A_11") (pintype "unspecified"))
      (node (ref "7SEG14") (pin "11") (pinfunction "A_11") (pintype "unspecified"))
      (node (ref "ICF") (pin "14") (pinfunction "SEG_A_14") (pintype "unspecified"))
    )
    (net (code "98") (name "F-B") (class "Default")
      (node (ref "7SEG13") (pin "7") (pinfunction "B_7") (pintype "unspecified"))
      (node (ref "7SEG14") (pin "7") (pinfunction "B_7") (pintype "unspecified"))
      (node (ref "ICF") (pin "16") (pinfunction "SEG_B_16") (pintype "unspecified"))
    )
    (net (code "99") (name "F-C") (class "Default")
      (node (ref "7SEG13") (pin "4") (pinfunction "C_4") (pintype "unspecified"))
      (node (ref "7SEG14") (pin "4") (pinfunction "C_4") (pintype "unspecified"))
      (node (ref "ICF") (pin "20") (pinfunction "SEG_C_20") (pintype "unspecified"))
    )
    (net (code "100") (name "F-D") (class "Default")
      (node (ref "7SEG13") (pin "2") (pinfunction "D_2") (pintype "unspecified"))
      (node (ref "7SEG14") (pin "2") (pinfunction "D_2") (pintype "unspecified"))
      (node (ref "ICF") (pin "23") (pinfunction "SEG_D_23") (pintype "unspecified"))
    )
    (net (code "101") (name "F-D1") (class "Default")
      (node (ref "7SEG14") (pin "12") (pinfunction "DIG.1_12") (pintype "unspecified"))
      (node (ref "ICF") (pin "2") (pinfunction "DIG0_2") (pintype "unspecified"))
    )
    (net (code "102") (name "F-D2") (class "Default")
      (node (ref "7SEG14") (pin "9") (pinfunction "DIG.2_9") (pintype "unspecified"))
      (node (ref "ICF") (pin "11") (pinfunction "DIG1_11") (pintype "unspecified"))
    )
    (net (code "103") (name "F-D3") (class "Default")
      (node (ref "7SEG14") (pin "8") (pinfunction "DIG.3_8") (pintype "unspecified"))
      (node (ref "ICF") (pin "6") (pinfunction "DIG2_6") (pintype "unspecified"))
    )
    (net (code "104") (name "F-D4") (class "Default")
      (node (ref "7SEG14") (pin "6") (pinfunction "DIG.4_6") (pintype "unspecified"))
      (node (ref "ICF") (pin "7") (pinfunction "DIG3_7") (pintype "unspecified"))
    )
    (net (code "105") (name "F-D5") (class "Default")
      (node (ref "7SEG13") (pin "12") (pinfunction "DIG.1_12") (pintype "unspecified"))
      (node (ref "ICF") (pin "3") (pinfunction "DIG4_3") (pintype "unspecified"))
    )
    (net (code "106") (name "F-D6") (class "Default")
      (node (ref "7SEG13") (pin "9") (pinfunction "DIG.2_9") (pintype "unspecified"))
      (node (ref "ICF") (pin "10") (pinfunction "DIG5_10") (pintype "unspecified"))
    )
    (net (code "107") (name "F-D7") (class "Default")
      (node (ref "7SEG13") (pin "8") (pinfunction "DIG.3_8") (pintype "unspecified"))
      (node (ref "ICF") (pin "5") (pinfunction "DIG6_5") (pintype "unspecified"))
    )
    (net (code "108") (name "F-D8") (class "Default")
      (node (ref "7SEG13") (pin "6") (pinfunction "DIG.4_6") (pintype "unspecified"))
      (node (ref "ICF") (pin "8") (pinfunction "DIG7_8") (pintype "unspecified"))
    )
    (net (code "109") (name "F-DP") (class "Default")
      (node (ref "7SEG13") (pin "3") (pinfunction "DP_3") (pintype "unspecified"))
      (node (ref "7SEG14") (pin "3") (pinfunction "DP_3") (pintype "unspecified"))
      (node (ref "ICF") (pin "22") (pinfunction "SEG_DP_22") (pintype "unspecified"))
    )
    (net (code "110") (name "F-E") (class "Default")
      (node (ref "7SEG13") (pin "1") (pinfunction "E_1") (pintype "unspecified"))
      (node (ref "7SEG14") (pin "1") (pinfunction "E_1") (pintype "unspecified"))
      (node (ref "ICF") (pin "21") (pinfunction "SEG_E_21") (pintype "unspecified"))
    )
    (net (code "111") (name "F-F") (class "Default")
      (node (ref "7SEG13") (pin "10") (pinfunction "F_10") (pintype "unspecified"))
      (node (ref "7SEG14") (pin "10") (pinfunction "F_10") (pintype "unspecified"))
      (node (ref "ICF") (pin "15") (pinfunction "SEG_F_15") (pintype "unspecified"))
    )
    (net (code "112") (name "F-G") (class "Default")
      (node (ref "7SEG13") (pin "5") (pinfunction "G_5") (pintype "unspecified"))
      (node (ref "7SEG14") (pin "5") (pinfunction "G_5") (pintype "unspecified"))
      (node (ref "ICF") (pin "17") (pinfunction "SEG_G_17") (pintype "unspecified"))
    )
    (net (code "113") (name "G-A") (class "Default")
      (node (ref "7SEG11") (pin "11") (pinfunction "A_11") (pintype "unspecified"))
      (node (ref "7SEG12") (pin "11") (pinfunction "A_11") (pintype "unspecified"))
      (node (ref "ICG") (pin "14") (pinfunction "SEG_A_14") (pintype "unspecified"))
    )
    (net (code "114") (name "G-B") (class "Default")
      (node (ref "7SEG11") (pin "7") (pinfunction "B_7") (pintype "unspecified"))
      (node (ref "7SEG12") (pin "7") (pinfunction "B_7") (pintype "unspecified"))
      (node (ref "ICG") (pin "16") (pinfunction "SEG_B_16") (pintype "unspecified"))
    )
    (net (code "115") (name "G-C") (class "Default")
      (node (ref "7SEG11") (pin "4") (pinfunction "C_4") (pintype "unspecified"))
      (node (ref "7SEG12") (pin "4") (pinfunction "C_4") (pintype "unspecified"))
      (node (ref "ICG") (pin "20") (pinfunction "SEG_C_20") (pintype "unspecified"))
    )
    (net (code "116") (name "G-D") (class "Default")
      (node (ref "7SEG11") (pin "2") (pinfunction "D_2") (pintype "unspecified"))
      (node (ref "7SEG12") (pin "2") (pinfunction "D_2") (pintype "unspecified"))
      (node (ref "ICG") (pin "23") (pinfunction "SEG_D_23") (pintype "unspecified"))
    )
    (net (code "117") (name "G-D1") (class "Default")
      (node (ref "7SEG11") (pin "12") (pinfunction "DIG.1_12") (pintype "unspecified"))
      (node (ref "ICG") (pin "2") (pinfunction "DIG0_2") (pintype "unspecified"))
    )
    (net (code "118") (name "G-D2") (class "Default")
      (node (ref "7SEG11") (pin "9") (pinfunction "DIG.2_9") (pintype "unspecified"))
      (node (ref "ICG") (pin "11") (pinfunction "DIG1_11") (pintype "unspecified"))
    )
    (net (code "119") (name "G-D3") (class "Default")
      (node (ref "7SEG11") (pin "8") (pinfunction "DIG.3_8") (pintype "unspecified"))
      (node (ref "ICG") (pin "6") (pinfunction "DIG2_6") (pintype "unspecified"))
    )
    (net (code "120") (name "G-D4") (class "Default")
      (node (ref "7SEG11") (pin "6") (pinfunction "DIG.4_6") (pintype "unspecified"))
      (node (ref "ICG") (pin "7") (pinfunction "DIG3_7") (pintype "unspecified"))
    )
    (net (code "121") (name "G-D5") (class "Default")
      (node (ref "7SEG12") (pin "12") (pinfunction "DIG.1_12") (pintype "unspecified"))
      (node (ref "ICG") (pin "3") (pinfunction "DIG4_3") (pintype "unspecified"))
    )
    (net (code "122") (name "G-D6") (class "Default")
      (node (ref "7SEG12") (pin "9") (pinfunction "DIG.2_9") (pintype "unspecified"))
      (node (ref "ICG") (pin "10") (pinfunction "DIG5_10") (pintype "unspecified"))
    )
    (net (code "123") (name "G-D7") (class "Default")
      (node (ref "7SEG12") (pin "8") (pinfunction "DIG.3_8") (pintype "unspecified"))
      (node (ref "ICG") (pin "5") (pinfunction "DIG6_5") (pintype "unspecified"))
    )
    (net (code "124") (name "G-D8") (class "Default")
      (node (ref "7SEG12") (pin "6") (pinfunction "DIG.4_6") (pintype "unspecified"))
      (node (ref "ICG") (pin "8") (pinfunction "DIG7_8") (pintype "unspecified"))
    )
    (net (code "125") (name "G-DP") (class "Default")
      (node (ref "7SEG11") (pin "3") (pinfunction "DP_3") (pintype "unspecified"))
      (node (ref "7SEG12") (pin "3") (pinfunction "DP_3") (pintype "unspecified"))
      (node (ref "ICG") (pin "22") (pinfunction "SEG_DP_22") (pintype "unspecified"))
    )
    (net (code "126") (name "G-E") (class "Default")
      (node (ref "7SEG11") (pin "1") (pinfunction "E_1") (pintype "unspecified"))
      (node (ref "7SEG12") (pin "1") (pinfunction "E_1") (pintype "unspecified"))
      (node (ref "ICG") (pin "21") (pinfunction "SEG_E_21") (pintype "unspecified"))
    )
    (net (code "127") (name "G-F") (class "Default")
      (node (ref "7SEG11") (pin "10") (pinfunction "F_10") (pintype "unspecified"))
      (node (ref "7SEG12") (pin "10") (pinfunction "F_10") (pintype "unspecified"))
      (node (ref "ICG") (pin "15") (pinfunction "SEG_F_15") (pintype "unspecified"))
    )
    (net (code "128") (name "G-G") (class "Default")
      (node (ref "7SEG11") (pin "5") (pinfunction "G_5") (pintype "unspecified"))
      (node (ref "7SEG12") (pin "5") (pinfunction "G_5") (pintype "unspecified"))
      (node (ref "ICG") (pin "17") (pinfunction "SEG_G_17") (pintype "unspecified"))
    )
    (net (code "129") (name "GND") (class "Default")
      (node (ref "C1") (pin "1") (pinfunction "1_1") (pintype "unspecified"))
      (node (ref "C10") (pin "2") (pinfunction "2_2") (pintype "unspecified"))
      (node (ref "C11") (pin "2") (pinfunction "2_2") (pintype "unspecified"))
      (node (ref "C12") (pin "1") (pinfunction "1_1") (pintype "unspecified"))
      (node (ref "C13") (pin "1") (pinfunction "1_1") (pintype "unspecified"))
      (node (ref "C14") (pin "2") (pinfunction "2_2") (pintype "unspecified"))
      (node (ref "C15") (pin "2") (pinfunction "2_2") (pintype "unspecified"))
      (node (ref "C16") (pin "1") (pinfunction "1_1") (pintype "unspecified"))
      (node (ref "C2") (pin "2") (pinfunction "2_2") (pintype "unspecified"))
      (node (ref "C3") (pin "2") (pinfunction "2_2") (pintype "unspecified"))
      (node (ref "C4") (pin "1") (pinfunction "1_1") (pintype "unspecified"))
      (node (ref "C5") (pin "1") (pinfunction "1_1") (pintype "unspecified"))
      (node (ref "C6") (pin "2") (pinfunction "2_2") (pintype "unspecified"))
      (node (ref "C7") (pin "2") (pinfunction "2_2") (pintype "unspecified"))
      (node (ref "C8") (pin "1") (pinfunction "1_1") (pintype "unspecified"))
      (node (ref "C9") (pin "1") (pinfunction "1_1") (pintype "unspecified"))
      (node (ref "ICA") (pin "4") (pinfunction "GND_4") (pintype "unspecified"))
      (node (ref "ICA") (pin "9") (pinfunction "GND_9") (pintype "unspecified"))
      (node (ref "ICB") (pin "4") (pinfunction "GND_4") (pintype "unspecified"))
      (node (ref "ICB") (pin "9") (pinfunction "GND_9") (pintype "unspecified"))
      (node (ref "ICC") (pin "4") (pinfunction "GND_4") (pintype "unspecified"))
      (node (ref "ICC") (pin "9") (pinfunction "GND_9") (pintype "unspecified"))
      (node (ref "ICD") (pin "4") (pinfunction "GND_4") (pintype "unspecified"))
      (node (ref "ICD") (pin "9") (pinfunction "GND_9") (pintype "unspecified"))
      (node (ref "ICE") (pin "4") (pinfunction "GND_4") (pintype "unspecified"))
      (node (ref "ICE") (pin "9") (pinfunction "GND_9") (pintype "unspecified"))
      (node (ref "ICF") (pin "4") (pinfunction "GND_4") (pintype "unspecified"))
      (node (ref "ICF") (pin "9") (pinfunction "GND_9") (pintype "unspecified"))
      (node (ref "ICG") (pin "4") (pinfunction "GND_4") (pintype "unspecified"))
      (node (ref "ICG") (pin "9") (pinfunction "GND_9") (pintype "unspecified"))
      (node (ref "ICH") (pin "4") (pinfunction "GND_4") (pintype "unspecified"))
      (node (ref "ICH") (pin "9") (pinfunction "GND_9") (pintype "unspecified"))
      (node (ref "POWER") (pin "1") (pinfunction "1_1") (pintype "unspecified"))
      (node (ref "POWER") (pin "2") (pinfunction "2_2") (pintype "unspecified"))
    )
    (net (code "130") (name "H-A") (class "Default")
      (node (ref "7SEG10") (pin "11") (pinfunction "A_11") (pintype "unspecified"))
      (node (ref "7SEG9") (pin "11") (pinfunction "A_11") (pintype "unspecified"))
      (node (ref "ICH") (pin "14") (pinfunction "SEG_A_14") (pintype "unspecified"))
    )
    (net (code "131") (name "H-B") (class "Default")
      (node (ref "7SEG10") (pin "7") (pinfunction "B_7") (pintype "unspecified"))
      (node (ref "7SEG9") (pin "7") (pinfunction "B_7") (pintype "unspecified"))
      (node (ref "ICH") (pin "16") (pinfunction "SEG_B_16") (pintype "unspecified"))
    )
    (net (code "132") (name "H-C") (class "Default")
      (node (ref "7SEG10") (pin "4") (pinfunction "C_4") (pintype "unspecified"))
      (node (ref "7SEG9") (pin "4") (pinfunction "C_4") (pintype "unspecified"))
      (node (ref "ICH") (pin "20") (pinfunction "SEG_C_20") (pintype "unspecified"))
    )
    (net (code "133") (name "H-D") (class "Default")
      (node (ref "7SEG10") (pin "2") (pinfunction "D_2") (pintype "unspecified"))
      (node (ref "7SEG9") (pin "2") (pinfunction "D_2") (pintype "unspecified"))
      (node (ref "ICH") (pin "23") (pinfunction "SEG_D_23") (pintype "unspecified"))
    )
    (net (code "134") (name "H-D1") (class "Default")
      (node (ref "7SEG10") (pin "12") (pinfunction "DIG.1_12") (pintype "unspecified"))
      (node (ref "ICH") (pin "2") (pinfunction "DIG0_2") (pintype "unspecified"))
    )
    (net (code "135") (name "H-D2") (class "Default")
      (node (ref "7SEG10") (pin "9") (pinfunction "DIG.2_9") (pintype "unspecified"))
      (node (ref "ICH") (pin "11") (pinfunction "DIG1_11") (pintype "unspecified"))
    )
    (net (code "136") (name "H-D3") (class "Default")
      (node (ref "7SEG10") (pin "8") (pinfunction "DIG.3_8") (pintype "unspecified"))
      (node (ref "ICH") (pin "6") (pinfunction "DIG2_6") (pintype "unspecified"))
    )
    (net (code "137") (name "H-D4") (class "Default")
      (node (ref "7SEG10") (pin "6") (pinfunction "DIG.4_6") (pintype "unspecified"))
      (node (ref "ICH") (pin "7") (pinfunction "DIG3_7") (pintype "unspecified"))
    )
    (net (code "138") (name "H-D5") (class "Default")
      (node (ref "7SEG9") (pin "12") (pinfunction "DIG.1_12") (pintype "unspecified"))
      (node (ref "ICH") (pin "3") (pinfunction "DIG4_3") (pintype "unspecified"))
    )
    (net (code "139") (name "H-D6") (class "Default")
      (node (ref "7SEG9") (pin "9") (pinfunction "DIG.2_9") (pintype "unspecified"))
      (node (ref "ICH") (pin "10") (pinfunction "DIG5_10") (pintype "unspecified"))
    )
    (net (code "140") (name "H-D7") (class "Default")
      (node (ref "7SEG9") (pin "8") (pinfunction "DIG.3_8") (pintype "unspecified"))
      (node (ref "ICH") (pin "5") (pinfunction "DIG6_5") (pintype "unspecified"))
    )
    (net (code "141") (name "H-D8") (class "Default")
      (node (ref "7SEG9") (pin "6") (pinfunction "DIG.4_6") (pintype "unspecified"))
      (node (ref "ICH") (pin "8") (pinfunction "DIG7_8") (pintype "unspecified"))
    )
    (net (code "142") (name "H-DP") (class "Default")
      (node (ref "7SEG10") (pin "3") (pinfunction "DP_3") (pintype "unspecified"))
      (node (ref "7SEG9") (pin "3") (pinfunction "DP_3") (pintype "unspecified"))
      (node (ref "ICH") (pin "22") (pinfunction "SEG_DP_22") (pintype "unspecified"))
    )
    (net (code "143") (name "H-E") (class "Default")
      (node (ref "7SEG10") (pin "1") (pinfunction "E_1") (pintype "unspecified"))
      (node (ref "7SEG9") (pin "1") (pinfunction "E_1") (pintype "unspecified"))
      (node (ref "ICH") (pin "21") (pinfunction "SEG_E_21") (pintype "unspecified"))
    )
    (net (code "144") (name "H-F") (class "Default")
      (node (ref "7SEG10") (pin "10") (pinfunction "F_10") (pintype "unspecified"))
      (node (ref "7SEG9") (pin "10") (pinfunction "F_10") (pintype "unspecified"))
      (node (ref "ICH") (pin "15") (pinfunction "SEG_F_15") (pintype "unspecified"))
    )
    (net (code "145") (name "H-G") (class "Default")
      (node (ref "7SEG10") (pin "5") (pinfunction "G_5") (pintype "unspecified"))
      (node (ref "7SEG9") (pin "5") (pinfunction "G_5") (pintype "unspecified"))
      (node (ref "ICH") (pin "17") (pinfunction "SEG_G_17") (pintype "unspecified"))
    )
    (net (code "146") (name "Load A (G)") (class "Default")
      (node (ref "HA-D") (pin "3") (pinfunction "3_3") (pintype "input"))
      (node (ref "ICA") (pin "12") (pinfunction "LOAD(CS#)_12") (pintype "unspecified"))
    )
    (net (code "147") (name "Load B (G)") (class "Default")
      (node (ref "HA-D") (pin "4") (pinfunction "4_4") (pintype "input"))
      (node (ref "ICB") (pin "12") (pinfunction "LOAD(CS#)_12") (pintype "unspecified"))
    )
    (net (code "148") (name "Load C (G)") (class "Default")
      (node (ref "HA-D") (pin "9") (pinfunction "9_9") (pintype "input"))
      (node (ref "ICC") (pin "12") (pinfunction "LOAD(CS#)_12") (pintype "unspecified"))
    )
    (net (code "149") (name "Load D (G)") (class "Default")
      (node (ref "HA-D") (pin "10") (pinfunction "10_10") (pintype "input"))
      (node (ref "ICD") (pin "12") (pinfunction "LOAD(CS#)_12") (pintype "unspecified"))
    )
    (net (code "150") (name "Load E (G)") (class "Default")
      (node (ref "HE-H") (pin "3") (pinfunction "3_3") (pintype "input"))
      (node (ref "ICE") (pin "12") (pinfunction "LOAD(CS#)_12") (pintype "unspecified"))
    )
    (net (code "151") (name "Load F (G)") (class "Default")
      (node (ref "HE-H") (pin "4") (pinfunction "4_4") (pintype "input"))
      (node (ref "ICF") (pin "12") (pinfunction "LOAD(CS#)_12") (pintype "unspecified"))
    )
    (net (code "152") (name "Load G (G)") (class "Default")
      (node (ref "HE-H") (pin "9") (pinfunction "9_9") (pintype "input"))
      (node (ref "ICG") (pin "12") (pinfunction "LOAD(CS#)_12") (pintype "unspecified"))
    )
    (net (code "153") (name "Load H (G)") (class "Default")
      (node (ref "HE-H") (pin "10") (pinfunction "10_10") (pintype "input"))
      (node (ref "ICH") (pin "12") (pinfunction "LOAD(CS#)_12") (pintype "unspecified"))
    )
    (net (code "154") (name "Net-(ICA-ISET)") (class "Default")
      (node (ref "ICA") (pin "18") (pinfunction "ISET_18") (pintype "unspecified"))
      (node (ref "R1") (pin "1") (pinfunction "1_1") (pintype "unspecified"))
    )
    (net (code "155") (name "Net-(ICB-ISET)") (class "Default")
      (node (ref "ICB") (pin "18") (pinfunction "ISET_18") (pintype "unspecified"))
      (node (ref "R2") (pin "1") (pinfunction "1_1") (pintype "unspecified"))
    )
    (net (code "156") (name "Net-(ICC-ISET)") (class "Default")
      (node (ref "ICC") (pin "18") (pinfunction "ISET_18") (pintype "unspecified"))
      (node (ref "R3") (pin "1") (pinfunction "1_1") (pintype "unspecified"))
    )
    (net (code "157") (name "Net-(ICD-ISET)") (class "Default")
      (node (ref "ICD") (pin "18") (pinfunction "ISET_18") (pintype "unspecified"))
      (node (ref "R4") (pin "1") (pinfunction "1_1") (pintype "unspecified"))
    )
    (net (code "158") (name "Net-(ICE-ISET)") (class "Default")
      (node (ref "ICE") (pin "18") (pinfunction "ISET_18") (pintype "unspecified"))
      (node (ref "R8") (pin "1") (pinfunction "1_1") (pintype "unspecified"))
    )
    (net (code "159") (name "Net-(ICF-ISET)") (class "Default")
      (node (ref "ICF") (pin "18") (pinfunction "ISET_18") (pintype "unspecified"))
      (node (ref "R7") (pin "1") (pinfunction "1_1") (pintype "unspecified"))
    )
    (net (code "160") (name "Net-(ICG-ISET)") (class "Default")
      (node (ref "ICG") (pin "18") (pinfunction "ISET_18") (pintype "unspecified"))
      (node (ref "R6") (pin "1") (pinfunction "1_1") (pintype "unspecified"))
    )
    (net (code "161") (name "Net-(ICH-ISET)") (class "Default")
      (node (ref "ICH") (pin "18") (pinfunction "ISET_18") (pintype "unspecified"))
      (node (ref "R5") (pin "1") (pinfunction "1_1") (pintype "unspecified"))
    )
    (net (code "162") (name "VCC") (class "Default")
      (node (ref "C1") (pin "2") (pinfunction "2_2") (pintype "unspecified"))
      (node (ref "C10") (pin "1") (pinfunction "1_1") (pintype "unspecified"))
      (node (ref "C11") (pin "1") (pinfunction "1_1") (pintype "unspecified"))
      (node (ref "C12") (pin "2") (pinfunction "2_2") (pintype "unspecified"))
      (node (ref "C13") (pin "2") (pinfunction "2_2") (pintype "unspecified"))
      (node (ref "C14") (pin "1") (pinfunction "1_1") (pintype "unspecified"))
      (node (ref "C15") (pin "1") (pinfunction "1_1") (pintype "unspecified"))
      (node (ref "C16") (pin "2") (pinfunction "2_2") (pintype "unspecified"))
      (node (ref "C2") (pin "1") (pinfunction "1_1") (pintype "unspecified"))
      (node (ref "C3") (pin "1") (pinfunction "1_1") (pintype "unspecified"))
      (node (ref "C4") (pin "2") (pinfunction "2_2") (pintype "unspecified"))
      (node (ref "C5") (pin "2") (pinfunction "2_2") (pintype "unspecified"))
      (node (ref "C6") (pin "1") (pinfunction "1_1") (pintype "unspecified"))
      (node (ref "C7") (pin "1") (pinfunction "1_1") (pintype "unspecified"))
      (node (ref "C8") (pin "2") (pinfunction "2_2") (pintype "unspecified"))
      (node (ref "C9") (pin "2") (pinfunction "2_2") (pintype "unspecified"))
      (node (ref "ICA") (pin "19") (pinfunction "V+_19") (pintype "unspecified"))
      (node (ref "ICB") (pin "19") (pinfunction "V+_19") (pintype "unspecified"))
      (node (ref "ICC") (pin "19") (pinfunction "V+_19") (pintype "unspecified"))
      (node (ref "ICD") (pin "19") (pinfunction "V+_19") (pintype "unspecified"))
      (node (ref "ICE") (pin "19") (pinfunction "V+_19") (pintype "unspecified"))
      (node (ref "ICF") (pin "19") (pinfunction "V+_19") (pintype "unspecified"))
      (node (ref "ICG") (pin "19") (pinfunction "V+_19") (pintype "unspecified"))
      (node (ref "ICH") (pin "19") (pinfunction "V+_19") (pintype "unspecified"))
      (node (ref "POWER") (pin "3") (pinfunction "3_3") (pintype "unspecified"))
      (node (ref "POWER") (pin "4") (pinfunction "4_4") (pintype "unspecified"))
      (node (ref "R1") (pin "2") (pinfunction "2_2") (pintype "unspecified"))
      (node (ref "R2") (pin "2") (pinfunction "2_2") (pintype "unspecified"))
      (node (ref "R3") (pin "2") (pinfunction "2_2") (pintype "unspecified"))
      (node (ref "R4") (pin "2") (pinfunction "2_2") (pintype "unspecified"))
      (node (ref "R5") (pin "2") (pinfunction "2_2") (pintype "unspecified"))
      (node (ref "R6") (pin "2") (pinfunction "2_2") (pintype "unspecified"))
      (node (ref "R7") (pin "2") (pinfunction "2_2") (pintype "unspecified"))
      (node (ref "R8") (pin "2") (pinfunction "2_2") (pintype "unspecified"))
    )
    (net (code "163") (name "unconnected-(ICA-DOUT-Pad24)") (class "Default")
      (node (ref "ICA") (pin "24") (pinfunction "DOUT_24") (pintype "unspecified+no_connect"))
    )
    (net (code "164") (name "unconnected-(ICB-DOUT-Pad24)") (class "Default")
      (node (ref "ICB") (pin "24") (pinfunction "DOUT_24") (pintype "unspecified+no_connect"))
    )
    (net (code "165") (name "unconnected-(ICC-DOUT-Pad24)") (class "Default")
      (node (ref "ICC") (pin "24") (pinfunction "DOUT_24") (pintype "unspecified+no_connect"))
    )
    (net (code "166") (name "unconnected-(ICD-DOUT-Pad24)") (class "Default")
      (node (ref "ICD") (pin "24") (pinfunction "DOUT_24") (pintype "unspecified+no_connect"))
    )
    (net (code "167") (name "unconnected-(ICE-DOUT-Pad24)") (class "Default")
      (node (ref "ICE") (pin "24") (pinfunction "DOUT_24") (pintype "unspecified+no_connect"))
    )
    (net (code "168") (name "unconnected-(ICF-DOUT-Pad24)") (class "Default")
      (node (ref "ICF") (pin "24") (pinfunction "DOUT_24") (pintype "unspecified+no_connect"))
    )
    (net (code "169") (name "unconnected-(ICG-DOUT-Pad24)") (class "Default")
      (node (ref "ICG") (pin "24") (pinfunction "DOUT_24") (pintype "unspecified+no_connect"))
    )
    (net (code "170") (name "unconnected-(ICH-DOUT-Pad24)") (class "Default")
      (node (ref "ICH") (pin "24") (pinfunction "DOUT_24") (pintype "unspecified+no_connect"))
    )
  )
)
